# CT310_V1_0.net
KiCad netlist of a schematic drawn in Altium Designer
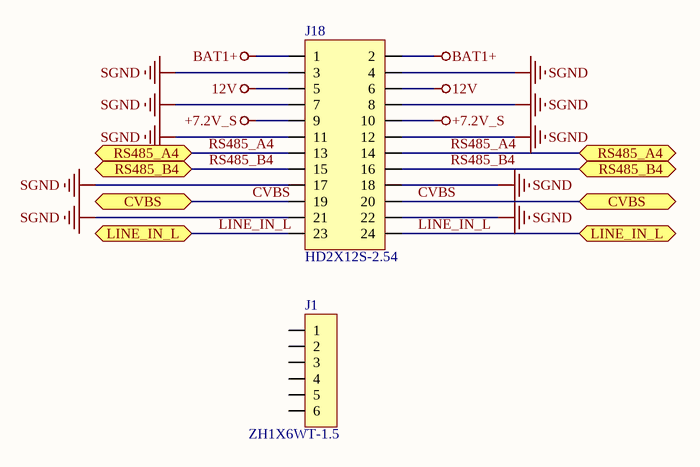
[diagram p0: CT310高端控制盒图数传接口电路V1.0.SchDoc]

(export (version "E")
  (design (tool "Eeschema 10.0.6"))
  (components
    (comp (ref "J1")
      (value "ZH1X6WT-1.5")
      (footprint "ZH1X6WT-1.5")
      (libsource (lib "Connector Class") (part "HEADER1X6"))
    )
    (comp (ref "J18")
      (value "HD2X12S-2.54")
      (footprint "HD2X12S-2.54")
      (libsource (lib "Connector Class") (part "HEADER2X12"))
    )
  )
  (nets
    (net (code "1") (name "+7.2V_S") (class "Default")
      (node (ref "J18") (pin "10") (pinfunction "10_10") (pintype "passive"))
      (node (ref "J18") (pin "9") (pinfunction "9_9") (pintype "passive"))
    )
    (net (code "2") (name "/CVBS") (class "Default")
      (node (ref "J18") (pin "19") (pinfunction "19_19") (pintype "passive"))
      (node (ref "J18") (pin "20") (pinfunction "20_20") (pintype "passive"))
    )
    (net (code "3") (name "/LINE_IN_L") (class "Default")
      (node (ref "J18") (pin "23") (pinfunction "23_23") (pintype "passive"))
      (node (ref "J18") (pin "24") (pinfunction "24_24") (pintype "passive"))
    )
    (net (code "4") (name "/RS485_A4") (class "Default")
      (node (ref "J18") (pin "13") (pinfunction "13_13") (pintype "passive"))
      (node (ref "J18") (pin "14") (pinfunction "14_14") (pintype "passive"))
    )
    (net (code "5") (name "/RS485_B4") (class "Default")
      (node (ref "J18") (pin "15") (pinfunction "15_15") (pintype "passive"))
      (node (ref "J18") (pin "16") (pinfunction "16_16") (pintype "passive"))
    )
    (net (code "6") (name "12V") (class "Default")
      (node (ref "J18") (pin "5") (pinfunction "5_5") (pintype "passive"))
      (node (ref "J18") (pin "6") (pinfunction "6_6") (pintype "passive"))
    )
    (net (code "7") (name "BAT1+") (class "Default")
      (node (ref "J18") (pin "1") (pinfunction "1_1") (pintype "passive"))
      (node (ref "J18") (pin "2") (pinfunction "2_2") (pintype "passive"))
    )
    (net (code "8") (name "SGND") (class "Default")
      (node (ref "J18") (pin "11") (pinfunction "11_11") (pintype "passive"))
      (node (ref "J18") (pin "12") (pinfunction "12_12") (pintype "passive"))
      (node (ref "J18") (pin "17") (pinfunction "17_17") (pintype "passive"))
      (node (ref "J18") (pin "18") (pinfunction "18_18") (pintype "passive"))
      (node (ref "J18") (pin "21") (pinfunction "21_21") (pintype "passive"))
      (node (ref "J18") (pin "22") (pinfunction "22_22") (pintype "passive"))
      (node (ref "J18") (pin "3") (pinfunction "3_3") (pintype "passive"))
      (node (ref "J18") (pin "4") (pinfunction "4_4") (pintype "passive"))
      (node (ref "J18") (pin "7") (pinfunction "7_7") (pintype "passive"))
      (node (ref "J18") (pin "8") (pinfunction "8_8") (pintype "passive"))
    )
    (net (code "9") (name "unconnected-(J1-Pad1)") (class "Default")
      (node (ref "J1") (pin "1") (pinfunction "1_1") (pintype "passive"))
    )
    (net (code "10") (name "unconnected-(J1-Pad2)") (class "Default")
      (node (ref "J1") (pin "2") (pinfunction "2_2") (pintype "passive"))
    )
    (net (code "11") (name "unconnected-(J1-Pad3)") (class "Default")
      (node (ref "J1") (pin "3") (pinfunction "3_3") (pintype "passive"))
    )
    (net (code "12") (name "unconnected-(J1-Pad4)") (class "Default")
      (node (ref "J1") (pin "4") (pinfunction "4_4") (pintype "passive"))
    )
    (net (code "13") (name "unconnected-(J1-Pad5)") (class "Default")
      (node (ref "J1") (pin "5") (pinfunction "5_5") (pintype "passive"))
    )
    (net (code "14") (name "unconnected-(J1-Pad6)") (class "Default")
      (node (ref "J1") (pin "6") (pinfunction "6_6") (pintype "passive"))
    )
  )
)
